# QCopterRC_FFCSPI_Sch.net
KiCad netlist of a schematic drawn in Altium Designer
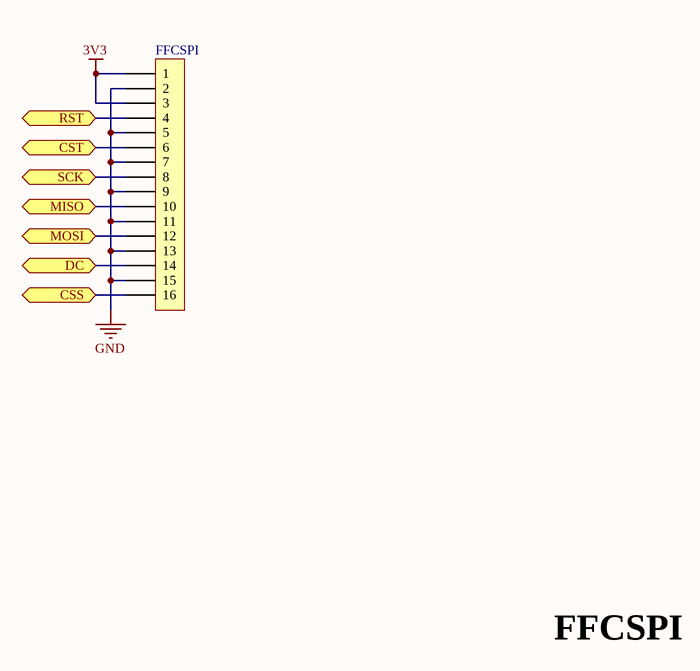
[diagram p0: QCopterRC_FFCSPI_Sch.SchDoc]

(export (version "E")
  (design (tool "Eeschema 10.0.6"))
  (components
    (comp (ref "FFCSPI")
      (value "FFC_0.5_16")
      (footprint "PCB_Connector:FFC_0.5_16")
      (description "FFC")
      (libsource (lib "SCH_Connector") (part "FFC_0.5_16"))
    )
  )
  (nets
    (net (code "1") (name "/CSS") (class "Default")
      (node (ref "FFCSPI") (pin "16") (pinfunction "16_16") (pintype "passive"))
    )
    (net (code "2") (name "/CST") (class "Default")
      (node (ref "FFCSPI") (pin "6") (pinfunction "6_6") (pintype "passive"))
    )
    (net (code "3") (name "/DC") (class "Default")
      (node (ref "FFCSPI") (pin "14") (pinfunction "14_14") (pintype "passive"))
    )
    (net (code "4") (name "/MISO") (class "Default")
      (node (ref "FFCSPI") (pin "10") (pinfunction "10_10") (pintype "passive"))
    )
    (net (code "5") (name "/MOSI") (class "Default")
      (node (ref "FFCSPI") (pin "12") (pinfunction "12_12") (pintype "passive"))
    )
    (net (code "6") (name "/RST") (class "Default")
      (node (ref "FFCSPI") (pin "4") (pinfunction "4_4") (pintype "passive"))
    )
    (net (code "7") (name "/SCK") (class "Default")
      (node (ref "FFCSPI") (pin "8") (pinfunction "8_8") (pintype "passive"))
    )
    (net (code "8") (name "3V3") (class "Default")
      (node (ref "FFCSPI") (pin "1") (pinfunction "1_1") (pintype "passive"))
      (node (ref "FFCSPI") (pin "3") (pinfunction "3_3") (pintype "passive"))
    )
    (net (code "9") (name "GND") (class "Default")
      (node (ref "FFCSPI") (pin "11") (pinfunction "11_11") (pintype "passive"))
      (node (ref "FFCSPI") (pin "13") (pinfunction "13_13") (pintype "passive"))
      (node (ref "FFCSPI") (pin "15") (pinfunction "15_15") (pintype "passive"))
      (node (ref "FFCSPI") (pin "2") (pinfunction "2_2") (pintype "passive"))
      (node (ref "FFCSPI") (pin "5") (pinfunction "5_5") (pintype "passive"))
      (node (ref "FFCSPI") (pin "7") (pinfunction "7_7") (pintype "passive"))
      (node (ref "FFCSPI") (pin "9") (pinfunction "9_9") (pintype "passive"))
    )
  )
)
